# Sheet1.net
KiCad netlist of a schematic drawn in Altium Designer
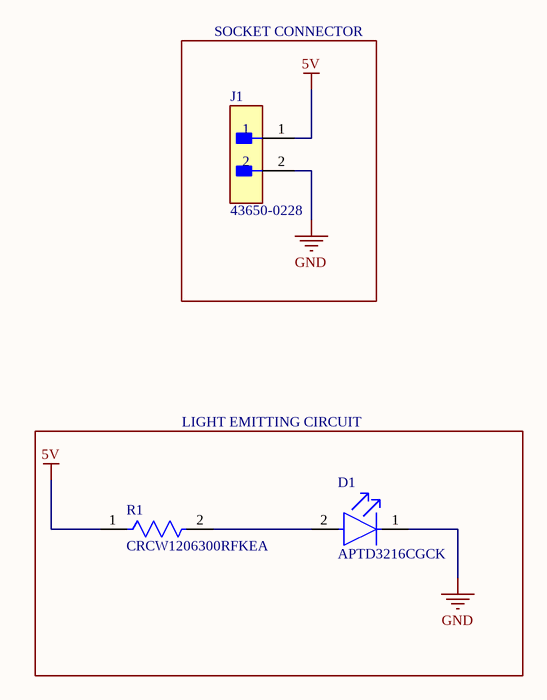
[diagram p0: Sheet1.SchDoc]

(export (version "E")
  (design (tool "Eeschema 10.0.6"))
  (components
    (comp (ref "D1")
      (value "APTD3216CGCK")
      (footprint "FP-APTD3216CGCK-MFG")
      (description "LED GREEN CLEAR 2SMD")
      (libsource (lib "Altium Content Vault") (part "8706943c75ba83719d021d2fdc84c58"))
    )
    (comp (ref "J1")
      (value "43650-0228")
      (footprint "FP-436500228-MFG")
      (description "CONN HEADER VERT 2POS 3MM")
      (libsource (lib "Altium Content Vault") (part "88c1139f9d239099ffebecbe3f7647a"))
    )
    (comp (ref "R1")
      (value "CRCW1206300RFKEA")
      (footprint "FP-CRCW1206-e3-IPC_A")
      (description "RES Thick Film, 300Ω, 1%, 0.25W, 100ppm/°C, 1206")
      (fields (field (name "TOLERANCE") "1%"))
      (libsource (lib "Altium Content Vault") (part "1029c3af85768c4190bb7ad29bc67b5"))
    )
  )
  (nets
    (net (code "1") (name "5V") (class "Default")
      (node (ref "J1") (pin "1") (pinfunction "1_1") (pintype "passive"))
      (node (ref "R1") (pin "1") (pinfunction "1_1") (pintype "passive"))
    )
    (net (code "2") (name "GND") (class "Default")
      (node (ref "D1") (pin "1") (pinfunction "C_1") (pintype "passive"))
      (node (ref "J1") (pin "2") (pinfunction "2_2") (pintype "passive"))
    )
    (net (code "3") (name "Net-(D1-A)") (class "Default")
      (node (ref "D1") (pin "2") (pinfunction "A_2") (pintype "passive"))
      (node (ref "R1") (pin "2") (pinfunction "2_2") (pintype "passive"))
    )
  )
)
